# electrodragon.net
KiCad netlist of a schematic drawn in EAGLE
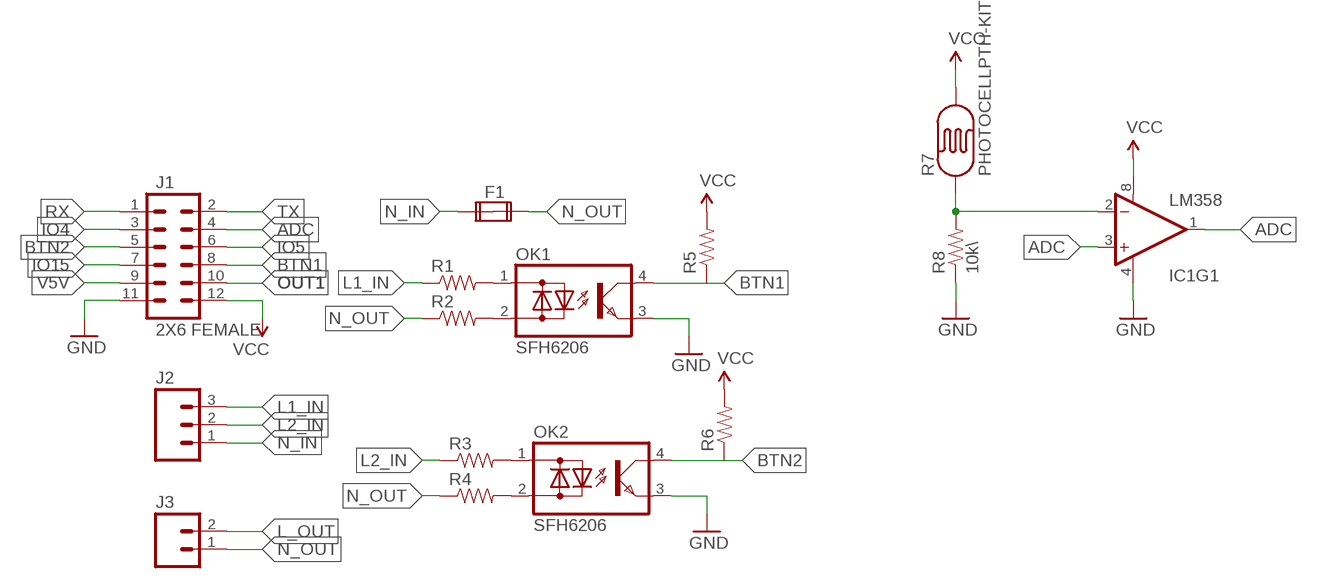
[diagram p0: schematic, sheet 1]

(export (version "E")
  (design (tool "Eeschema 10.0.6"))
  (components
    (comp (ref "F1")
      (value "FUSE2P")
      (footprint "eagle-import:FUSE1")
      (libsource (lib "eagle-import") (part "FUSE2P"))
    )
    (comp (ref "IC1")
      (value "LM358")
      (footprint "eagle-import:DIP08")
      (libsource (lib "eagle-import") (part "LM358"))
    )
    (comp (ref "J1")
      (value "2X6 FEMALE")
      (footprint "eagle-import:2X6")
      (libsource (lib "eagle-import") (part "M06X2PTH_FEMALE"))
    )
    (comp (ref "J2")
      (value "M03-SCREW-5MM")
      (footprint "eagle-import:SCREWTERMINAL-5MM-3")
      (libsource (lib "eagle-import") (part "M03-SCREW-5MM"))
    )
    (comp (ref "J3")
      (value "M025MM")
      (footprint "eagle-import:SCREWTERMINAL-5MM-2")
      (libsource (lib "eagle-import") (part "M025MM"))
    )
    (comp (ref "OK1")
      (value "SFH6206")
      (footprint "eagle-import:DIL4-SMD")
      (libsource (lib "eagle-import") (part "SFH6206"))
    )
    (comp (ref "OK2")
      (value "SFH6206")
      (footprint "eagle-import:DIL4-SMD")
      (libsource (lib "eagle-import") (part "SFH6206"))
    )
    (comp (ref "R1")
      (value "RESISTORPTH-1/2W")
      (footprint "eagle-import:AXIAL-0.5")
      (libsource (lib "eagle-import") (part "RESISTORPTH-1/2W"))
    )
    (comp (ref "R2")
      (value "RESISTORPTH-1/2W")
      (footprint "eagle-import:AXIAL-0.5")
      (libsource (lib "eagle-import") (part "RESISTORPTH-1/2W"))
    )
    (comp (ref "R3")
      (value "RESISTORPTH-1/2W")
      (footprint "eagle-import:AXIAL-0.5")
      (libsource (lib "eagle-import") (part "RESISTORPTH-1/2W"))
    )
    (comp (ref "R4")
      (value "RESISTORPTH-1/2W")
      (footprint "eagle-import:AXIAL-0.5")
      (libsource (lib "eagle-import") (part "RESISTORPTH-1/2W"))
    )
    (comp (ref "R5")
      (value "RESISTOR0805-RES")
      (footprint "eagle-import:0805")
      (libsource (lib "eagle-import") (part "RESISTOR0805-RES"))
    )
    (comp (ref "R6")
      (value "RESISTOR0805-RES")
      (footprint "eagle-import:0805")
      (libsource (lib "eagle-import") (part "RESISTOR0805-RES"))
    )
    (comp (ref "R7")
      (value "PHOTOCELLPTH-KIT")
      (footprint "eagle-import:PHOTOCELL-KIT")
      (libsource (lib "eagle-import") (part "PHOTOCELLPTH-KIT"))
    )
    (comp (ref "R8")
      (value "10k\\")
      (footprint "eagle-import:0805")
      (libsource (lib "eagle-import") (part "RESISTOR0805-RES"))
    )
  )
  (nets
    (net (code "1") (name "ADC") (class "Default")
      (node (ref "IC1") (pin "1") (pinfunction "OUT_1") (pintype "output"))
      (node (ref "IC1") (pin "3") (pinfunction "+IN_3") (pintype "input"))
      (node (ref "J1") (pin "4") (pinfunction "4_4") (pintype "passive"))
    )
    (net (code "2") (name "BTN1") (class "Default")
      (node (ref "J1") (pin "8") (pinfunction "8_8") (pintype "passive"))
      (node (ref "OK1") (pin "4") (pinfunction "C_4") (pintype "passive"))
    )
    (net (code "3") (name "BTN2") (class "Default")
      (node (ref "J1") (pin "5") (pinfunction "5_5") (pintype "passive"))
      (node (ref "OK2") (pin "4") (pinfunction "C_4") (pintype "passive"))
    )
    (net (code "4") (name "GND") (class "Default")
      (node (ref "IC1") (pin "4") (pinfunction "V-_4") (pintype "power_in"))
      (node (ref "J1") (pin "11") (pinfunction "11_11") (pintype "passive"))
      (node (ref "OK1") (pin "3") (pinfunction "E_3") (pintype "passive"))
      (node (ref "OK2") (pin "3") (pinfunction "E_3") (pintype "passive"))
      (node (ref "R8") (pin "1") (pinfunction "1_1") (pintype "passive"))
    )
    (net (code "5") (name "IO4") (class "Default")
      (node (ref "J1") (pin "3") (pinfunction "3_3") (pintype "passive"))
    )
    (net (code "6") (name "IO5") (class "Default")
      (node (ref "J1") (pin "6") (pinfunction "6_6") (pintype "passive"))
    )
    (net (code "7") (name "IO15") (class "Default")
      (node (ref "J1") (pin "7") (pinfunction "7_7") (pintype "passive"))
    )
    (net (code "8") (name "L1_IN") (class "Default")
      (node (ref "J2") (pin "3") (pinfunction "3_3") (pintype "passive"))
      (node (ref "R1") (pin "P$1") (pinfunction "1_P$1") (pintype "passive"))
    )
    (net (code "9") (name "L2_IN") (class "Default")
      (node (ref "J2") (pin "2") (pinfunction "2_2") (pintype "passive"))
      (node (ref "R3") (pin "P$1") (pinfunction "1_P$1") (pintype "passive"))
    )
    (net (code "10") (name "L_OUT") (class "Default")
      (node (ref "J3") (pin "2") (pinfunction "2_2") (pintype "passive"))
    )
    (net (code "11") (name "N_IN") (class "Default")
      (node (ref "F1") (pin "1A") (pinfunction "1A_1A") (pintype "passive"))
      (node (ref "J2") (pin "1") (pinfunction "1_1") (pintype "passive"))
    )
    (net (code "12") (name "N_OUT") (class "Default")
      (node (ref "F1") (pin "2A") (pinfunction "2A_2A") (pintype "passive"))
      (node (ref "J3") (pin "1") (pinfunction "1_1") (pintype "passive"))
      (node (ref "R2") (pin "P$1") (pinfunction "1_P$1") (pintype "passive"))
      (node (ref "R4") (pin "P$1") (pinfunction "1_P$1") (pintype "passive"))
    )
    (net (code "13") (name "Net-(IC1A--IN)") (class "Default")
      (node (ref "IC1") (pin "2") (pinfunction "-IN_2") (pintype "input"))
      (node (ref "R7") (pin "1") (pinfunction "P$1_1") (pintype "bidirectional"))
      (node (ref "R8") (pin "2") (pinfunction "2_2") (pintype "passive"))
    )
    (net (code "14") (name "Net-(OK1-AC1)") (class "Default")
      (node (ref "OK1") (pin "1") (pinfunction "AC1_1") (pintype "passive"))
      (node (ref "R1") (pin "P$2") (pinfunction "2_P$2") (pintype "passive"))
    )
    (net (code "15") (name "Net-(OK1-AC2)") (class "Default")
      (node (ref "OK1") (pin "2") (pinfunction "AC2_2") (pintype "passive"))
      (node (ref "R2") (pin "P$2") (pinfunction "2_P$2") (pintype "passive"))
    )
    (net (code "16") (name "Net-(OK2-AC1)") (class "Default")
      (node (ref "OK2") (pin "1") (pinfunction "AC1_1") (pintype "passive"))
      (node (ref "R3") (pin "P$2") (pinfunction "2_P$2") (pintype "passive"))
    )
    (net (code "17") (name "Net-(OK2-AC2)") (class "Default")
      (node (ref "OK2") (pin "2") (pinfunction "AC2_2") (pintype "passive"))
      (node (ref "R4") (pin "P$2") (pinfunction "2_P$2") (pintype "passive"))
    )
    (net (code "18") (name "OUT1") (class "Default")
      (node (ref "J1") (pin "10") (pinfunction "10_10") (pintype "passive"))
    )
    (net (code "19") (name "RX") (class "Default")
      (node (ref "J1") (pin "1") (pinfunction "1_1") (pintype "passive"))
    )
    (net (code "20") (name "TX") (class "Default")
      (node (ref "J1") (pin "2") (pinfunction "2_2") (pintype "passive"))
    )
    (net (code "21") (name "V5V") (class "Default")
      (node (ref "J1") (pin "9") (pinfunction "9_9") (pintype "passive"))
    )
    (net (code "22") (name "VCC") (class "Default")
      (node (ref "IC1") (pin "8") (pinfunction "V+_8") (pintype "power_in"))
      (node (ref "J1") (pin "12") (pinfunction "12_12") (pintype "passive"))
      (node (ref "R5") (pin "2") (pinfunction "2_2") (pintype "passive"))
      (node (ref "R6") (pin "2") (pinfunction "2_2") (pintype "passive"))
      (node (ref "R7") (pin "2") (pinfunction "P$2_2") (pintype "bidirectional"))
    )
    (net (code "23") (name "unconnected-(F1-Pad1B)") (class "Default")
      (node (ref "F1") (pin "1B") (pinfunction "1B_1B") (pintype "passive"))
    )
    (net (code "24") (name "unconnected-(F1-Pad2B)") (class "Default")
      (node (ref "F1") (pin "2B") (pinfunction "2B_2B") (pintype "passive"))
    )
    (net (code "25") (name "unconnected-(R5-Pad1)") (class "Default")
      (node (ref "R5") (pin "1") (pinfunction "1_1") (pintype "passive"))
    )
    (net (code "26") (name "unconnected-(R6-Pad1)") (class "Default")
      (node (ref "R6") (pin "1") (pinfunction "1_1") (pintype "passive"))
    )
  )
)
